# PicoMiteVGAV1_0.net
KiCad netlist of a schematic drawn in EasyEDA Pro
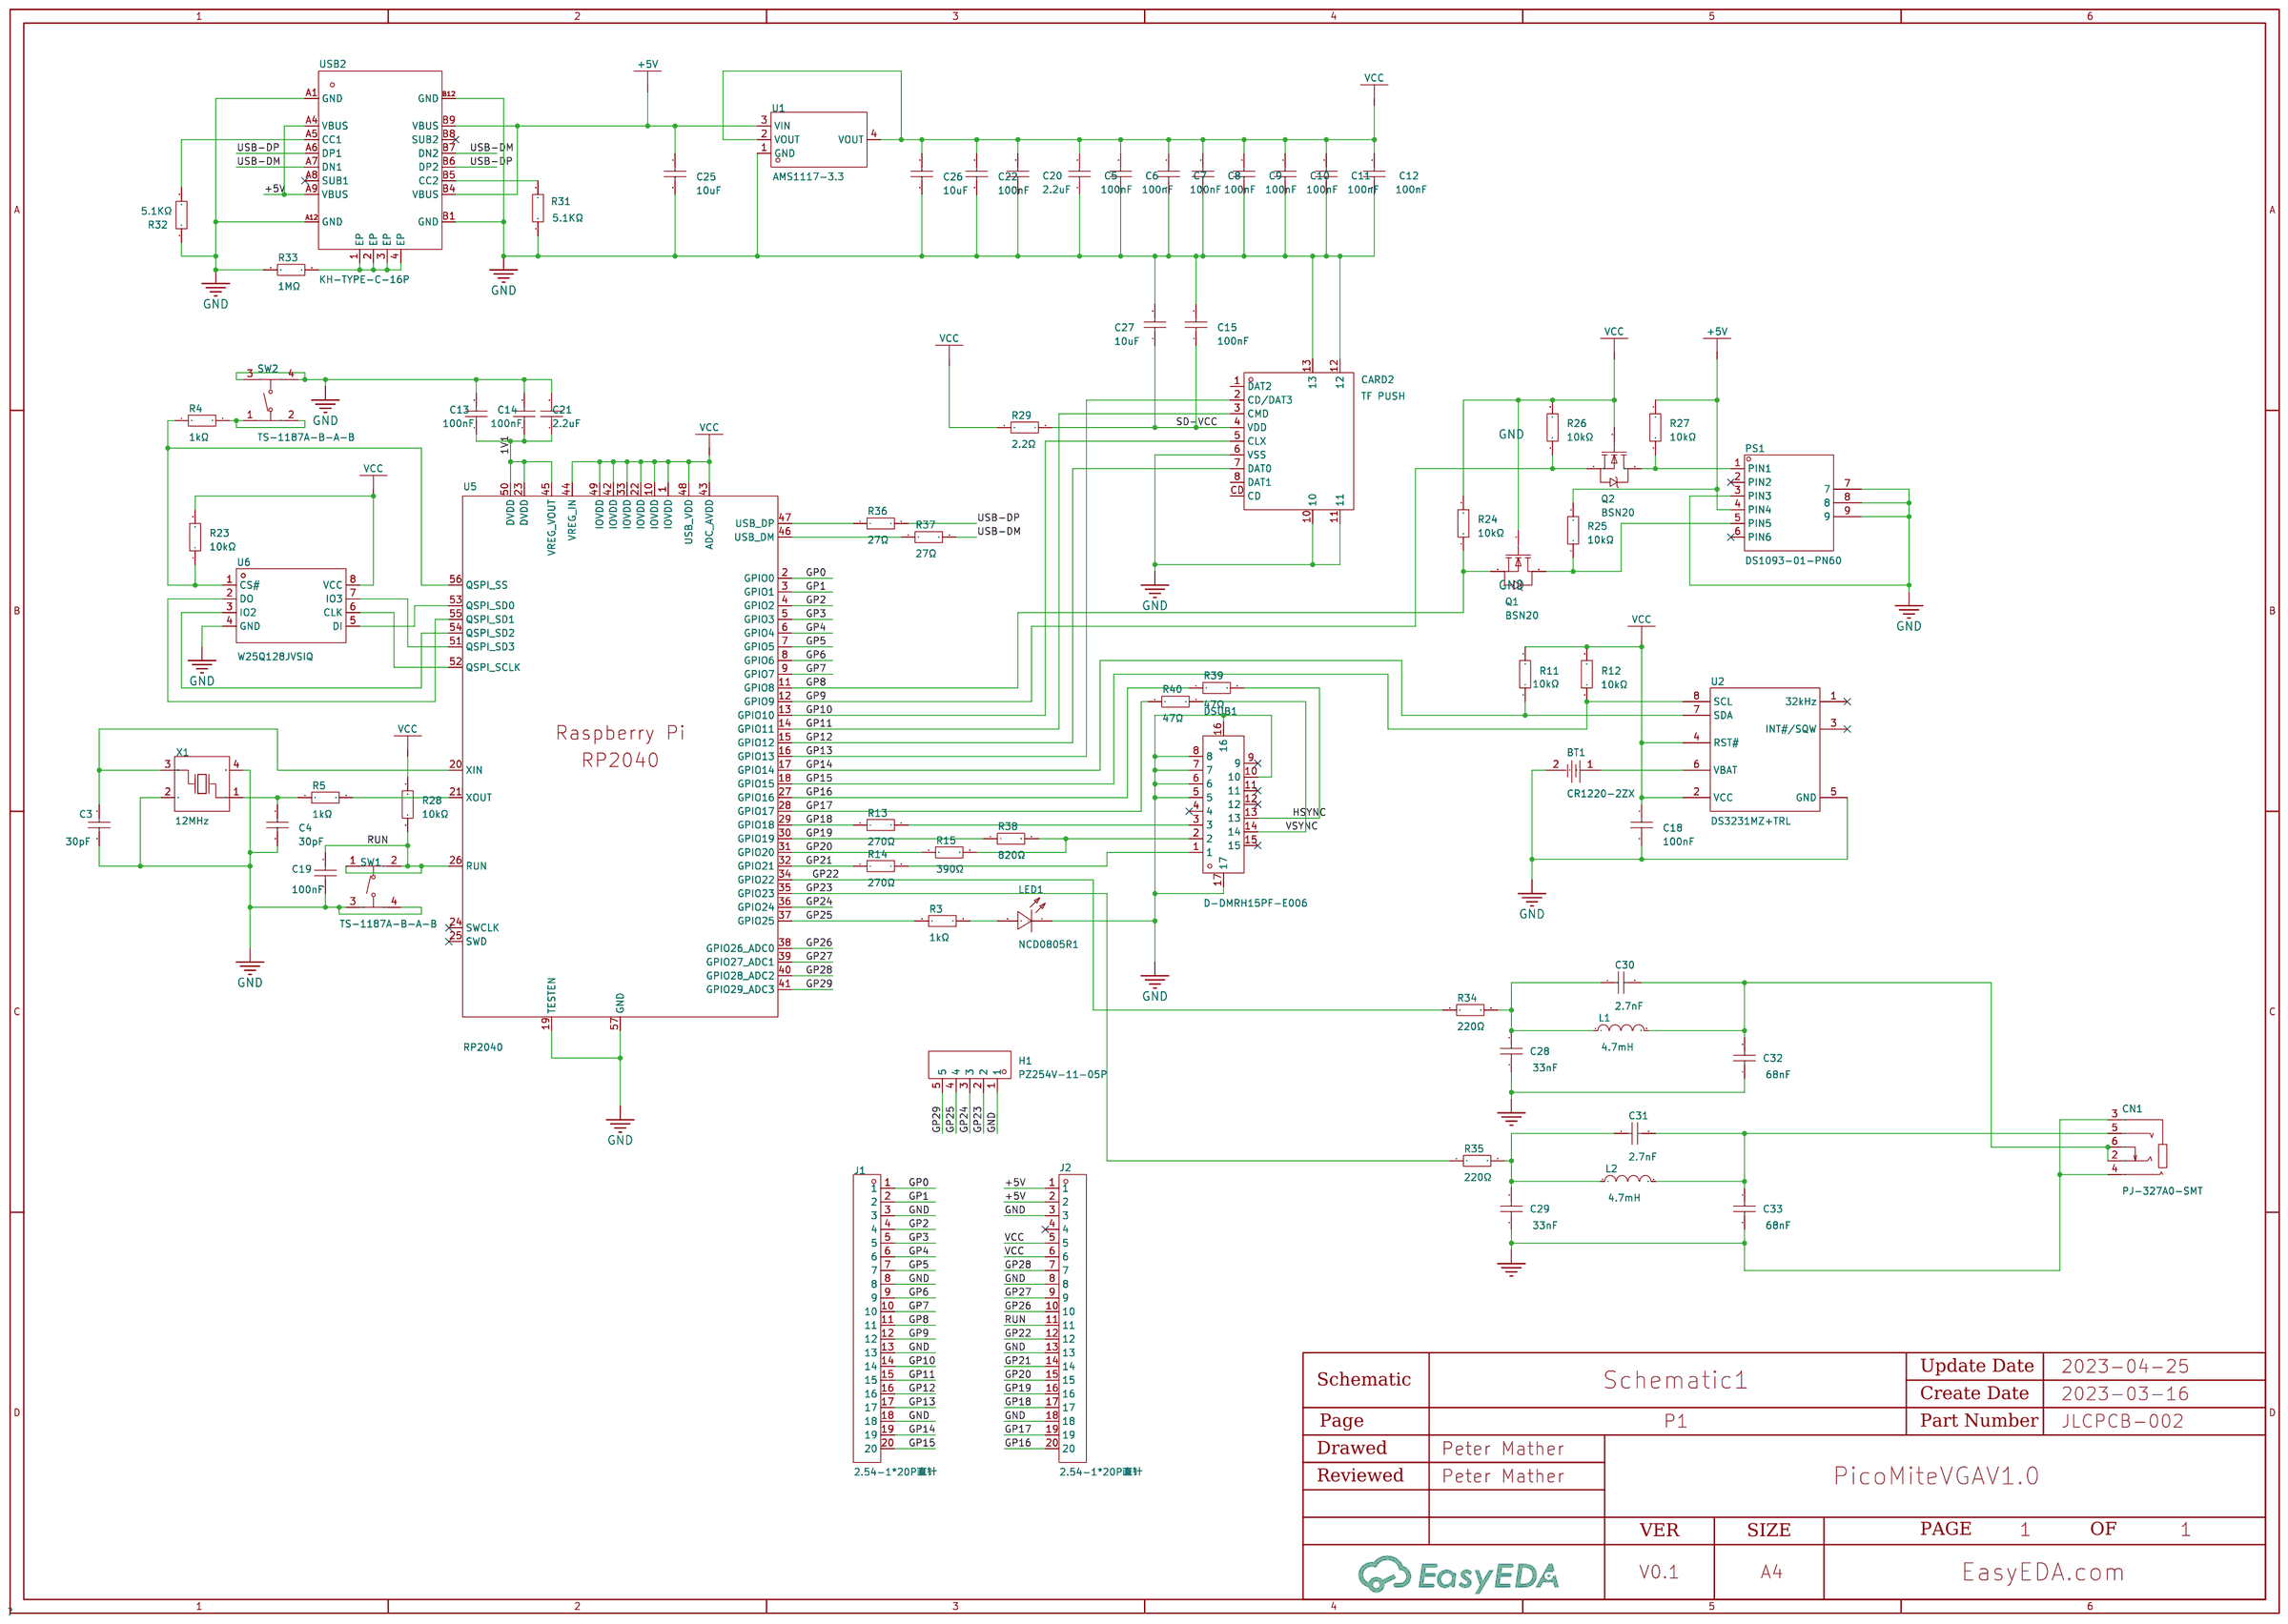
[diagram p0: schematic sheet]

(export (version "E")
  (design (tool "Eeschema 10.0.6"))
  (components
    (comp (ref "BT1")
      (value "CR1220-2ZX")
      (footprint "easyedapro:BAT-SMD_CR1220-2ZX")
      (fields (field (name "Manufacturer") "Q&J"))
      (libsource (lib "easyedapro") (part "CR1220-2ZX"))
    )
    (comp (ref "C3")
      (value "30pF")
      (footprint "easyedapro:C0805")
      (fields (field (name "Manufacturer Part") "0402CG300J500NT") (field (name "Manufacturer") "FH(风华)"))
      (libsource (lib "easyedapro") (part "CC0805JRNPO9BN300"))
    )
    (comp (ref "C4")
      (value "30pF")
      (footprint "easyedapro:C0805")
      (fields (field (name "Manufacturer Part") "0402CG300J500NT") (field (name "Manufacturer") "FH(风华)"))
      (libsource (lib "easyedapro") (part "CC0805JRNPO9BN300"))
    )
    (comp (ref "C5")
      (value "100nF")
      (footprint "easyedapro:C0603")
      (fields
        (field (name "Manufacturer Part") "CL05B104KO5NNNC")
        (field (name "Manufacturer") "SAMSUNG(三星)")
      )
      (libsource (lib "easyedapro") (part "CL10A225KO8NNNC"))
    )
    (comp (ref "C6")
      (value "100nF")
      (footprint "easyedapro:C0603")
      (fields
        (field (name "Manufacturer Part") "CL05B104KO5NNNC")
        (field (name "Manufacturer") "SAMSUNG(三星)")
      )
      (libsource (lib "easyedapro") (part "CL10A225KO8NNNC"))
    )
    (comp (ref "C7")
      (value "100nF")
      (footprint "easyedapro:C0603")
      (fields
        (field (name "Manufacturer Part") "CL05B104KO5NNNC")
        (field (name "Manufacturer") "SAMSUNG(三星)")
      )
      (libsource (lib "easyedapro") (part "CL10A225KO8NNNC"))
    )
    (comp (ref "C8")
      (value "100nF")
      (footprint "easyedapro:C0603")
      (fields
        (field (name "Manufacturer Part") "CL05B104KO5NNNC")
        (field (name "Manufacturer") "SAMSUNG(三星)")
      )
      (libsource (lib "easyedapro") (part "CL10A225KO8NNNC"))
    )
    (comp (ref "C9")
      (value "100nF")
      (footprint "easyedapro:C0603")
      (fields
        (field (name "Manufacturer Part") "CL05B104KO5NNNC")
        (field (name "Manufacturer") "SAMSUNG(三星)")
      )
      (libsource (lib "easyedapro") (part "CL10A225KO8NNNC"))
    )
    (comp (ref "C10")
      (value "100nF")
      (footprint "easyedapro:C0603")
      (fields
        (field (name "Manufacturer Part") "CL05B104KO5NNNC")
        (field (name "Manufacturer") "SAMSUNG(三星)")
      )
      (libsource (lib "easyedapro") (part "CL10A225KO8NNNC"))
    )
    (comp (ref "C11")
      (value "100nF")
      (footprint "easyedapro:C0603")
      (fields
        (field (name "Manufacturer Part") "CL05B104KO5NNNC")
        (field (name "Manufacturer") "SAMSUNG(三星)")
      )
      (libsource (lib "easyedapro") (part "CL10A225KO8NNNC"))
    )
    (comp (ref "C12")
      (value "100nF")
      (footprint "easyedapro:C0603")
      (fields
        (field (name "Manufacturer Part") "CL05B104KO5NNNC")
        (field (name "Manufacturer") "SAMSUNG(三星)")
      )
      (libsource (lib "easyedapro") (part "CL10A225KO8NNNC"))
    )
    (comp (ref "C13")
      (value "100nF")
      (footprint "easyedapro:C0603")
      (fields
        (field (name "Manufacturer Part") "CL05B104KO5NNNC")
        (field (name "Manufacturer") "SAMSUNG(三星)")
      )
      (libsource (lib "easyedapro") (part "CL10A225KO8NNNC"))
    )
    (comp (ref "C14")
      (value "100nF")
      (footprint "easyedapro:C0603")
      (fields
        (field (name "Manufacturer Part") "CL05B104KO5NNNC")
        (field (name "Manufacturer") "SAMSUNG(三星)")
      )
      (libsource (lib "easyedapro") (part "CL10A225KO8NNNC"))
    )
    (comp (ref "C15")
      (value "100nF")
      (footprint "easyedapro:C0603")
      (fields
        (field (name "Manufacturer Part") "CL05B104KO5NNNC")
        (field (name "Manufacturer") "SAMSUNG(三星)")
      )
      (libsource (lib "easyedapro") (part "CL10A225KO8NNNC"))
    )
    (comp (ref "C18")
      (value "100nF")
      (footprint "easyedapro:C0603")
      (fields
        (field (name "Manufacturer Part") "CL05B104KO5NNNC")
        (field (name "Manufacturer") "SAMSUNG(三星)")
      )
      (libsource (lib "easyedapro") (part "CL10A225KO8NNNC"))
    )
    (comp (ref "C19")
      (value "100nF")
      (footprint "easyedapro:C0603")
      (fields
        (field (name "Manufacturer Part") "CL05B104KO5NNNC")
        (field (name "Manufacturer") "SAMSUNG(三星)")
      )
      (libsource (lib "easyedapro") (part "CL10A225KO8NNNC"))
    )
    (comp (ref "C20")
      (value "2.2uF")
      (footprint "easyedapro:C0402_NEW")
      (fields
        (field (name "Manufacturer Part") "CL10A225KO8NNNC")
        (field (name "Manufacturer") "SAMSUNG(三星)")
      )
      (libsource (lib "easyedapro") (part "CL05B104KO5NNNC"))
    )
    (comp (ref "C21")
      (value "2.2uF")
      (footprint "easyedapro:C0402_NEW")
      (fields
        (field (name "Manufacturer Part") "CL10A225KO8NNNC")
        (field (name "Manufacturer") "SAMSUNG(三星)")
      )
      (libsource (lib "easyedapro") (part "CL05B104KO5NNNC"))
    )
    (comp (ref "C22")
      (value "100nF")
      (footprint "easyedapro:C0603")
      (fields
        (field (name "Manufacturer Part") "CL05B104KO5NNNC")
        (field (name "Manufacturer") "SAMSUNG(三星)")
      )
      (libsource (lib "easyedapro") (part "CL10A225KO8NNNC"))
    )
    (comp (ref "C25")
      (value "10uF")
      (footprint "easyedapro:C1206")
      (fields
        (field (name "Manufacturer Part") "CL31A106KBHNNNE")
        (field (name "Manufacturer") "SAMSUNG(三星)")
      )
      (libsource (lib "easyedapro") (part "CL31A106KBHNNNE"))
    )
    (comp (ref "C26")
      (value "10uF")
      (footprint "easyedapro:C1206")
      (fields
        (field (name "Manufacturer Part") "CL31A106KBHNNNE")
        (field (name "Manufacturer") "SAMSUNG(三星)")
      )
      (libsource (lib "easyedapro") (part "CL31A106KBHNNNE"))
    )
    (comp (ref "C27")
      (value "10uF")
      (footprint "easyedapro:C1206")
      (fields
        (field (name "Manufacturer Part") "CL31A106KBHNNNE")
        (field (name "Manufacturer") "SAMSUNG(三星)")
      )
      (libsource (lib "easyedapro") (part "CL31A106KBHNNNE"))
    )
    (comp (ref "C28")
      (value "33nF")
      (footprint "easyedapro:C0603")
      (fields
        (field (name "Manufacturer Part") "CL10B333KB8NNNC")
        (field (name "Manufacturer") "SAMSUNG(三星)")
        (field (name "Tolerance") "±10%")
      )
      (libsource (lib "easyedapro") (part "CL10B333KB8NNNC"))
    )
    (comp (ref "C29")
      (value "33nF")
      (footprint "easyedapro:C0603")
      (fields
        (field (name "Manufacturer Part") "CL10B333KB8NNNC")
        (field (name "Manufacturer") "SAMSUNG(三星)")
      )
      (libsource (lib "easyedapro") (part "CL10B333KB8NNNC"))
    )
    (comp (ref "C30")
      (value "2.7nF")
      (footprint "easyedapro:C0603")
      (fields (field (name "Manufacturer Part") "0603B272K500NT") (field (name "Manufacturer") "FH(风华)"))
      (libsource (lib "easyedapro") (part "0603B272K500NT"))
    )
    (comp (ref "C31")
      (value "2.7nF")
      (footprint "easyedapro:C0603")
      (fields (field (name "Manufacturer Part") "0603B272K500NT") (field (name "Manufacturer") "FH(风华)"))
      (libsource (lib "easyedapro") (part "0603B272K500NT"))
    )
    (comp (ref "C32")
      (value "68nF")
      (footprint "easyedapro:C0603")
      (fields
        (field (name "Manufacturer Part") "CL10B683KB8NNNC")
        (field (name "Manufacturer") "SAMSUNG(三星)")
        (field (name "Tolerance") "±10%")
      )
      (libsource (lib "easyedapro") (part "CL10B683KB8NNNC"))
    )
    (comp (ref "C33")
      (value "68nF")
      (footprint "easyedapro:C0603")
      (fields
        (field (name "Manufacturer Part") "CL10B683KB8NNNC")
        (field (name "Manufacturer") "SAMSUNG(三星)")
      )
      (libsource (lib "easyedapro") (part "CL10B683KB8NNNC"))
    )
    (comp (ref "CARD2")
      (value "TF PUSH")
      (footprint "easyedapro:TF-SMD_TF-PUSH")
      (fields (field (name "Manufacturer") "SHOU HAN(首韩)"))
      (libsource (lib "easyedapro") (part "TF PUSH"))
    )
    (comp (ref "CN1")
      (value "PJ-327A0-SMT")
      (footprint "easyedapro:AUDIO-SMD_PJ-327A0-SMT")
      (fields (field (name "Manufacturer") "XKB Connectivity(中国星坤)"))
      (libsource (lib "easyedapro") (part "PJ-327A0-SMT"))
    )
    (comp (ref "DSUB1")
      (value "D-DMRH15PF-E006")
      (footprint "easyedapro:DSUB-TH_15P-P2.29-H-F_DDMRH15PFE006")
      (fields (field (name "Manufacturer") "Ckmtw(灿科盟)"))
      (libsource (lib "easyedapro") (part "DDMRH15PFE006"))
    )
    (comp (ref "H1")
      (value "PZ254V-11-05P")
      (footprint "easyedapro:HDR-TH_5P-P2.54-V-M")
      (fields (field (name "Manufacturer") "XFCN(兴飞)"))
      (libsource (lib "easyedapro") (part "PZ254V-11-05P"))
    )
    (comp (ref "J1")
      (value "2.54-1*20P直针")
      (footprint "easyedapro:HDR-TH_20P-P2.54-V-M-1")
      (fields (field (name "Manufacturer") "BOOMELE(博穆精密)"))
      (libsource (lib "easyedapro") (part "Header-Male-2.54_1x20"))
    )
    (comp (ref "J2")
      (value "2.54-1*20P直针")
      (footprint "easyedapro:HDR-TH_20P-P2.54-V-M-1")
      (fields (field (name "Manufacturer") "BOOMELE(博穆精密)"))
      (libsource (lib "easyedapro") (part "Header-Male-2.54_1x20"))
    )
    (comp (ref "L1")
      (value "4.7mH")
      (footprint "easyedapro:IND-SMD_L6.0-W6.0")
      (fields (field (name "Manufacturer Part") "YNR6045-472M") (field (name "Manufacturer") "YJYCOIN(益嘉源)"))
      (libsource (lib "easyedapro") (part "YNR6045-472M"))
    )
    (comp (ref "L2")
      (value "4.7mH")
      (footprint "easyedapro:IND-SMD_L6.0-W6.0")
      (fields (field (name "Manufacturer Part") "YNR6045-472M") (field (name "Manufacturer") "YJYCOIN(益嘉源)"))
      (libsource (lib "easyedapro") (part "YNR6045-472M"))
    )
    (comp (ref "LED1")
      (value "NCD0805R1")
      (footprint "easyedapro:LED0805-RD")
      (description "Emitted Color:红灯")
      (fields (field (name "Manufacturer") "国星光电"))
      (libsource (lib "easyedapro") (part "FC-2012HRK-620D"))
    )
    (comp (ref "PS1")
      (value "DS1093-01-PN60")
      (footprint "easyedapro:CONN-TH_DS1093-01-PN60")
      (fields (field (name "Manufacturer") "CONNFLY"))
      (libsource (lib "easyedapro") (part "DS1093-01-PN60"))
    )
    (comp (ref "Q1")
      (value "BSN20")
      (footprint "easyedapro:SOT-23-3_L2.9-W1.6-P1.90-LS2.8-BR")
      (fields (field (name "Manufacturer") "SHIKUES(时科)"))
      (libsource (lib "easyedapro") (part "BSN20"))
    )
    (comp (ref "Q2")
      (value "BSN20")
      (footprint "easyedapro:SOT-23-3_L2.9-W1.6-P1.90-LS2.8-BR")
      (fields (field (name "Manufacturer") "SHIKUES(时科)"))
      (libsource (lib "easyedapro") (part "BSN20"))
    )
    (comp (ref "R3")
      (value "1kΩ")
      (footprint "easyedapro:R0603")
      (fields
        (field (name "Manufacturer Part") "0603WAF1001T5E")
        (field (name "Manufacturer") "UNI-ROYAL(厚声)")
      )
      (libsource (lib "easyedapro") (part "0603WAF1001T5E"))
    )
    (comp (ref "R4")
      (value "1kΩ")
      (footprint "easyedapro:R0603")
      (fields
        (field (name "Manufacturer Part") "0603WAF1001T5E")
        (field (name "Manufacturer") "UNI-ROYAL(厚声)")
      )
      (libsource (lib "easyedapro") (part "0603WAF1001T5E"))
    )
    (comp (ref "R5")
      (value "1kΩ")
      (footprint "easyedapro:R0603")
      (fields
        (field (name "Manufacturer Part") "0603WAF1001T5E")
        (field (name "Manufacturer") "UNI-ROYAL(厚声)")
      )
      (libsource (lib "easyedapro") (part "0603WAF1001T5E"))
    )
    (comp (ref "R11")
      (value "10kΩ")
      (footprint "easyedapro:R0805")
      (fields
        (field (name "Manufacturer Part") "0805W8F1002T5E")
        (field (name "Manufacturer") "UNI-ROYAL(厚声)")
      )
      (libsource (lib "easyedapro") (part "0805W8F1002T5E"))
    )
    (comp (ref "R12")
      (value "10kΩ")
      (footprint "easyedapro:R0805")
      (fields
        (field (name "Manufacturer Part") "0805W8F1002T5E")
        (field (name "Manufacturer") "UNI-ROYAL(厚声)")
      )
      (libsource (lib "easyedapro") (part "0805W8F1002T5E"))
    )
    (comp (ref "R13")
      (value "270Ω")
      (footprint "easyedapro:R0603")
      (fields
        (field (name "Manufacturer Part") "0603WAF2700T5E")
        (field (name "Manufacturer") "UNI-ROYAL(厚声)")
      )
      (libsource (lib "easyedapro") (part "0603WAF2700T5E"))
    )
    (comp (ref "R14")
      (value "270Ω")
      (footprint "easyedapro:R0603")
      (fields
        (field (name "Manufacturer Part") "0603WAF2700T5E")
        (field (name "Manufacturer") "UNI-ROYAL(厚声)")
      )
      (libsource (lib "easyedapro") (part "0603WAF2700T5E"))
    )
    (comp (ref "R15")
      (value "390Ω")
      (footprint "easyedapro:R0603")
      (fields
        (field (name "Manufacturer Part") "0603WAF3900T5E")
        (field (name "Manufacturer") "UNI-ROYAL(厚声)")
      )
      (libsource (lib "easyedapro") (part "0603WAF3900T5E"))
    )
    (comp (ref "R23")
      (value "10kΩ")
      (footprint "easyedapro:R0402")
      (fields
        (field (name "Manufacturer Part") "0402WGF1002TCE")
        (field (name "Manufacturer") "UNI-ROYAL(厚声)")
      )
      (libsource (lib "easyedapro") (part "0402WGF1002TCE"))
    )
    (comp (ref "R24")
      (value "10kΩ")
      (footprint "easyedapro:R0402")
      (fields
        (field (name "Manufacturer Part") "0402WGF1002TCE")
        (field (name "Manufacturer") "UNI-ROYAL(厚声)")
      )
      (libsource (lib "easyedapro") (part "0402WGF1002TCE"))
    )
    (comp (ref "R25")
      (value "10kΩ")
      (footprint "easyedapro:R0402")
      (fields
        (field (name "Manufacturer Part") "0402WGF1002TCE")
        (field (name "Manufacturer") "UNI-ROYAL(厚声)")
      )
      (libsource (lib "easyedapro") (part "0402WGF1002TCE"))
    )
    (comp (ref "R26")
      (value "10kΩ")
      (footprint "easyedapro:R0402")
      (fields
        (field (name "Manufacturer Part") "0402WGF1002TCE")
        (field (name "Manufacturer") "UNI-ROYAL(厚声)")
      )
      (libsource (lib "easyedapro") (part "0402WGF1002TCE"))
    )
    (comp (ref "R27")
      (value "10kΩ")
      (footprint "easyedapro:R0402")
      (fields
        (field (name "Manufacturer Part") "0402WGF1002TCE")
        (field (name "Manufacturer") "UNI-ROYAL(厚声)")
      )
      (libsource (lib "easyedapro") (part "0402WGF1002TCE"))
    )
    (comp (ref "R28")
      (value "10kΩ")
      (footprint "easyedapro:R0402")
      (fields
        (field (name "Manufacturer Part") "0402WGF1002TCE")
        (field (name "Manufacturer") "UNI-ROYAL(厚声)")
      )
      (libsource (lib "easyedapro") (part "0402WGF1002TCE"))
    )
    (comp (ref "R29")
      (value "2.2Ω")
      (footprint "easyedapro:R0805")
      (fields (field (name "Manufacturer") "UNI-ROYAL(厚声)"))
      (libsource (lib "easyedapro") (part "0805W8F220KT5E"))
    )
    (comp (ref "R31")
      (value "5.1kΩ")
      (footprint "easyedapro:R0603")
      (fields
        (field (name "Manufacturer Part") "5.1KΩ")
        (field (name "Manufacturer") "UNI-ROYAL(厚声)")
        (field (name "Tolerance") "±1%")
      )
      (libsource (lib "easyedapro") (part "0603WAF5101T5E"))
    )
    (comp (ref "R32")
      (value "5.1kΩ")
      (footprint "easyedapro:R0603")
      (fields
        (field (name "Manufacturer Part") "5.1KΩ")
        (field (name "Manufacturer") "UNI-ROYAL(厚声)")
        (field (name "Tolerance") "±1%")
      )
      (libsource (lib "easyedapro") (part "0603WAF5101T5E"))
    )
    (comp (ref "R33")
      (value "1MΩ")
      (footprint "easyedapro:R0603")
      (fields
        (field (name "Manufacturer Part") "0402WGF1004TCE")
        (field (name "Manufacturer") "UNI-ROYAL(厚声)")
        (field (name "Tolerance") "±1%")
      )
      (libsource (lib "easyedapro") (part "0603WAF1004T5E"))
    )
    (comp (ref "R34")
      (value "220Ω")
      (footprint "easyedapro:R0603")
      (fields
        (field (name "Manufacturer Part") "0603WAF2200T5E")
        (field (name "Manufacturer") "UNI-ROYAL(厚声)")
      )
      (libsource (lib "easyedapro") (part "0603WAF2200T5E"))
    )
    (comp (ref "R35")
      (value "220Ω")
      (footprint "easyedapro:R0603")
      (fields
        (field (name "Manufacturer Part") "0603WAF2200T5E")
        (field (name "Manufacturer") "UNI-ROYAL(厚声)")
      )
      (libsource (lib "easyedapro") (part "0603WAF2200T5E"))
    )
    (comp (ref "R36")
      (value "27Ω")
      (footprint "easyedapro:R0603")
      (fields
        (field (name "Manufacturer Part") "0603WAF270JT5E")
        (field (name "Manufacturer") "UNI-ROYAL(厚声)")
      )
      (libsource (lib "easyedapro") (part "0603WAF270JT5E"))
    )
    (comp (ref "R37")
      (value "27Ω")
      (footprint "easyedapro:R0603")
      (fields
        (field (name "Manufacturer Part") "0603WAF270JT5E")
        (field (name "Manufacturer") "UNI-ROYAL(厚声)")
      )
      (libsource (lib "easyedapro") (part "0603WAF270JT5E"))
    )
    (comp (ref "R38")
      (value "820Ω")
      (footprint "easyedapro:R0603")
      (fields
        (field (name "Manufacturer Part") "0603WAF8200T5E")
        (field (name "Manufacturer") "UNI-ROYAL(厚声)")
      )
      (libsource (lib "easyedapro") (part "0603WAF8200T5E"))
    )
    (comp (ref "R39")
      (value "47Ω")
      (footprint "easyedapro:R0805")
      (fields
        (field (name "Manufacturer Part") "0805W8F470JT5E")
        (field (name "Manufacturer") "UNI-ROYAL(厚声)")
      )
      (libsource (lib "easyedapro") (part "0805W8F470JT5E"))
    )
    (comp (ref "R40")
      (value "47Ω")
      (footprint "easyedapro:R0805")
      (fields
        (field (name "Manufacturer Part") "0805W8F470JT5E")
        (field (name "Manufacturer") "UNI-ROYAL(厚声)")
      )
      (libsource (lib "easyedapro") (part "0805W8F470JT5E"))
    )
    (comp (ref "SW1")
      (value "TS-1187A-B-A-B")
      (footprint "easyedapro:SW-SMD_4P-L5.1-W5.1-P3.70-LS6.5-TL-2")
      (fields (field (name "Manufacturer") "XKB Connectivity(中国星坤)"))
      (libsource (lib "easyedapro") (part "TS-1187A-B-A-B"))
    )
    (comp (ref "SW2")
      (value "TS-1187A-B-A-B")
      (footprint "easyedapro:SW-SMD_4P-L5.1-W5.1-P3.70-LS6.5-TL-2")
      (fields (field (name "Manufacturer") "XKB Connectivity(中国星坤)"))
      (libsource (lib "easyedapro") (part "TS-1187A-B-A-B"))
    )
    (comp (ref "U1")
      (value "AMS1117-3.3")
      (footprint "easyedapro:SOT-223-3_L6.5-W3.4-P2.30-LS7.0-BR")
      (fields (field (name "Manufacturer") "AMS"))
      (libsource (lib "easyedapro") (part "AMS1117-3.3"))
    )
    (comp (ref "U2")
      (value "DS3231MZ+TRL")
      (footprint "easyedapro:SOIC-8_L4.9-W3.9-P1.27-LS6.0-BL")
      (fields (field (name "Manufacturer") "MAXIM(美信)"))
      (libsource (lib "easyedapro") (part "DS3231MZ+"))
    )
    (comp (ref "U5")
      (value "RP2040")
      (footprint "easyedapro:LQFN-56_L7.0-W7.0-P0.4-EP")
      (fields (field (name "Manufacturer") "Raspberry Pi(树莓派)"))
      (libsource (lib "easyedapro") (part "RP2040"))
    )
    (comp (ref "U6")
      (value "W25Q128JVSIQ")
      (footprint "easyedapro:SOIC-8_L5.3-W5.3-P1.27-LS8.0-BL")
      (fields (field (name "Manufacturer") "WINBOND(华邦)"))
      (libsource (lib "easyedapro") (part "W25Q128JVSIQTR"))
    )
    (comp (ref "USB2")
      (value "KH-TYPE-C-16P")
      (footprint "easyedapro:USB-C-SMD_KH-TYPE-C-16P")
      (fields (field (name "Manufacturer") "kinghelm(金航标)"))
      (libsource (lib "easyedapro") (part "KH-TYPE-C-16P"))
    )
    (comp (ref "X1")
      (value "12MHz")
      (footprint "easyedapro:OSC-SMD_4P-L3.2-W2.5-BL")
      (fields (field (name "Manufacturer Part") "X322512MSB4SI") (field (name "Manufacturer") "YXC(扬兴晶振)"))
      (libsource (lib "easyedapro") (part "X322512MSB4SI"))
    )
  )
  (nets
    (net (code "1") (name "+5V") (class "Default")
      (node (ref "C25") (pin "2") (pinfunction "2_2") (pintype "input"))
      (node (ref "J2") (pin "1") (pinfunction "1_1") (pintype "input"))
      (node (ref "J2") (pin "2") (pinfunction "2_2") (pintype "input"))
      (node (ref "PS1") (pin "4") (pinfunction "PIN4_4") (pintype "input"))
      (node (ref "R25") (pin "2") (pinfunction "2_2") (pintype "input"))
      (node (ref "R27") (pin "2") (pinfunction "2_2") (pintype "input"))
      (node (ref "U1") (pin "3") (pinfunction "VIN_3") (pintype "input"))
      (node (ref "USB2") (pin "A4") (pinfunction "VBUS_A4") (pintype "input"))
      (node (ref "USB2") (pin "A9") (pinfunction "VBUS_A9") (pintype "input"))
      (node (ref "USB2") (pin "B4") (pinfunction "VBUS_B4") (pintype "input"))
      (node (ref "USB2") (pin "B9") (pinfunction "VBUS_B9") (pintype "input"))
    )
    (net (code "2") (name "/1V1") (class "Default")
      (node (ref "C13") (pin "1") (pinfunction "1_1") (pintype "input"))
      (node (ref "C14") (pin "1") (pinfunction "1_1") (pintype "input"))
      (node (ref "C21") (pin "1") (pinfunction "1_1") (pintype "input"))
      (node (ref "U5") (pin "23") (pinfunction "DVDD_23") (pintype "bidirectional"))
      (node (ref "U5") (pin "45") (pinfunction "VREG_VOUT_45") (pintype "bidirectional"))
      (node (ref "U5") (pin "50") (pinfunction "DVDD_50") (pintype "bidirectional"))
    )
    (net (code "3") (name "/GP0") (class "Default")
      (node (ref "J1") (pin "1") (pinfunction "1_1") (pintype "input"))
      (node (ref "U5") (pin "2") (pinfunction "GPIO0_2") (pintype "bidirectional"))
    )
    (net (code "4") (name "/GP1") (class "Default")
      (node (ref "J1") (pin "2") (pinfunction "2_2") (pintype "input"))
      (node (ref "U5") (pin "3") (pinfunction "GPIO1_3") (pintype "bidirectional"))
    )
    (net (code "5") (name "/GP2") (class "Default")
      (node (ref "J1") (pin "4") (pinfunction "4_4") (pintype "input"))
      (node (ref "U5") (pin "4") (pinfunction "GPIO2_4") (pintype "bidirectional"))
    )
    (net (code "6") (name "/GP3") (class "Default")
      (node (ref "J1") (pin "5") (pinfunction "5_5") (pintype "input"))
      (node (ref "U5") (pin "5") (pinfunction "GPIO3_5") (pintype "bidirectional"))
    )
    (net (code "7") (name "/GP4") (class "Default")
      (node (ref "J1") (pin "6") (pinfunction "6_6") (pintype "input"))
      (node (ref "U5") (pin "6") (pinfunction "GPIO4_6") (pintype "bidirectional"))
    )
    (net (code "8") (name "/GP5") (class "Default")
      (node (ref "J1") (pin "7") (pinfunction "7_7") (pintype "input"))
      (node (ref "U5") (pin "7") (pinfunction "GPIO5_7") (pintype "bidirectional"))
    )
    (net (code "9") (name "/GP6") (class "Default")
      (node (ref "J1") (pin "9") (pinfunction "9_9") (pintype "input"))
      (node (ref "U5") (pin "8") (pinfunction "GPIO6_8") (pintype "bidirectional"))
    )
    (net (code "10") (name "/GP7") (class "Default")
      (node (ref "J1") (pin "10") (pinfunction "10_10") (pintype "input"))
      (node (ref "U5") (pin "9") (pinfunction "GPIO7_9") (pintype "bidirectional"))
    )
    (net (code "11") (name "/GP8") (class "Default")
      (node (ref "J1") (pin "11") (pinfunction "11_11") (pintype "input"))
      (node (ref "Q1") (pin "2") (pinfunction "S_2") (pintype "input"))
      (node (ref "R24") (pin "1") (pinfunction "1_1") (pintype "input"))
      (node (ref "U5") (pin "11") (pinfunction "GPIO8_11") (pintype "bidirectional"))
    )
    (net (code "12") (name "/GP9") (class "Default")
      (node (ref "J1") (pin "12") (pinfunction "12_12") (pintype "input"))
      (node (ref "Q2") (pin "2") (pinfunction "S_2") (pintype "input"))
      (node (ref "R26") (pin "1") (pinfunction "1_1") (pintype "input"))
      (node (ref "U5") (pin "12") (pinfunction "GPIO9_12") (pintype "bidirectional"))
    )
    (net (code "13") (name "/GP10") (class "Default")
      (node (ref "CARD2") (pin "5") (pinfunction "CLX_5") (pintype "input"))
      (node (ref "J1") (pin "14") (pinfunction "14_14") (pintype "input"))
      (node (ref "U5") (pin "13") (pinfunction "GPIO10_13") (pintype "bidirectional"))
    )
    (net (code "14") (name "/GP11") (class "Default")
      (node (ref "CARD2") (pin "3") (pinfunction "CMD_3") (pintype "input"))
      (node (ref "J1") (pin "15") (pinfunction "15_15") (pintype "input"))
      (node (ref "U5") (pin "14") (pinfunction "GPIO11_14") (pintype "bidirectional"))
    )
    (net (code "15") (name "/GP12") (class "Default")
      (node (ref "CARD2") (pin "7") (pinfunction "DAT0_7") (pintype "input"))
      (node (ref "J1") (pin "16") (pinfunction "16_16") (pintype "input"))
      (node (ref "U5") (pin "15") (pinfunction "GPIO12_15") (pintype "bidirectional"))
    )
    (net (code "16") (name "/GP13") (class "Default")
      (node (ref "CARD2") (pin "2") (pinfunction "CD/DAT3_2") (pintype "input"))
      (node (ref "J1") (pin "17") (pinfunction "17_17") (pintype "input"))
      (node (ref "U5") (pin "16") (pinfunction "GPIO13_16") (pintype "bidirectional"))
    )
    (net (code "17") (name "/GP14") (class "Default")
      (node (ref "J1") (pin "19") (pinfunction "19_19") (pintype "input"))
      (node (ref "R11") (pin "1") (pinfunction "1_1") (pintype "input"))
      (node (ref "U2") (pin "7") (pinfunction "SDA_7") (pintype "bidirectional"))
      (node (ref "U5") (pin "17") (pinfunction "GPIO14_17") (pintype "bidirectional"))
    )
    (net (code "18") (name "/GP15") (class "Default")
      (node (ref "J1") (pin "20") (pinfunction "20_20") (pintype "input"))
      (node (ref "R12") (pin "1") (pinfunction "1_1") (pintype "input"))
      (node (ref "U2") (pin "8") (pinfunction "SCL_8") (pintype "input"))
      (node (ref "U5") (pin "18") (pinfunction "GPIO15_18") (pintype "bidirectional"))
    )
    (net (code "19") (name "/GP16") (class "Default")
      (node (ref "J2") (pin "20") (pinfunction "20_20") (pintype "input"))
      (node (ref "R39") (pin "1") (pinfunction "1_1") (pintype "input"))
      (node (ref "U5") (pin "27") (pinfunction "GPIO16_27") (pintype "bidirectional"))
    )
    (net (code "20") (name "/GP17") (class "Default")
      (node (ref "J2") (pin "19") (pinfunction "19_19") (pintype "input"))
      (node (ref "R40") (pin "1") (pinfunction "1_1") (pintype "input"))
      (node (ref "U5") (pin "28") (pinfunction "GPIO17_28") (pintype "bidirectional"))
    )
    (net (code "21") (name "/GP18") (class "Default")
      (node (ref "J2") (pin "17") (pinfunction "17_17") (pintype "input"))
      (node (ref "R13") (pin "1") (pinfunction "1_1") (pintype "input"))
      (node (ref "U5") (pin "29") (pinfunction "GPIO18_29") (pintype "bidirectional"))
    )
    (net (code "22") (name "/GP19") (class "Default")
      (node (ref "J2") (pin "16") (pinfunction "16_16") (pintype "input"))
      (node (ref "R38") (pin "1") (pinfunction "1_1") (pintype "input"))
      (node (ref "U5") (pin "30") (pinfunction "GPIO19_30") (pintype "bidirectional"))
    )
    (net (code "23") (name "/GP20") (class "Default")
      (node (ref "J2") (pin "15") (pinfunction "15_15") (pintype "input"))
      (node (ref "R15") (pin "1") (pinfunction "1_1") (pintype "input"))
      (node (ref "U5") (pin "31") (pinfunction "GPIO20_31") (pintype "bidirectional"))
    )
    (net (code "24") (name "/GP21") (class "Default")
      (node (ref "J2") (pin "14") (pinfunction "14_14") (pintype "input"))
      (node (ref "R14") (pin "1") (pinfunction "1_1") (pintype "input"))
      (node (ref "U5") (pin "32") (pinfunction "GPIO21_32") (pintype "bidirectional"))
    )
    (net (code "25") (name "/GP22") (class "Default")
      (node (ref "J2") (pin "12") (pinfunction "12_12") (pintype "input"))
      (node (ref "R34") (pin "1") (pinfunction "1_1") (pintype "input"))
      (node (ref "U5") (pin "34") (pinfunction "GPIO22_34") (pintype "bidirectional"))
    )
    (net (code "26") (name "/GP23") (class "Default")
      (node (ref "H1") (pin "2") (pinfunction "2_2") (pintype "input"))
      (node (ref "R35") (pin "1") (pinfunction "1_1") (pintype "input"))
      (node (ref "U5") (pin "35") (pinfunction "GPIO23_35") (pintype "bidirectional"))
    )
    (net (code "27") (name "/GP24") (class "Default")
      (node (ref "H1") (pin "3") (pinfunction "3_3") (pintype "input"))
      (node (ref "U5") (pin "36") (pinfunction "GPIO24_36") (pintype "bidirectional"))
    )
    (net (code "28") (name "/GP25") (class "Default")
      (node (ref "H1") (pin "4") (pinfunction "4_4") (pintype "input"))
      (node (ref "R3") (pin "1") (pinfunction "1_1") (pintype "input"))
      (node (ref "U5") (pin "37") (pinfunction "GPIO25_37") (pintype "bidirectional"))
    )
    (net (code "29") (name "/GP26") (class "Default")
      (node (ref "J2") (pin "10") (pinfunction "10_10") (pintype "input"))
      (node (ref "U5") (pin "38") (pinfunction "GPIO26_ADC0_38") (pintype "bidirectional"))
    )
    (net (code "30") (name "/GP27") (class "Default")
      (node (ref "J2") (pin "9") (pinfunction "9_9") (pintype "input"))
      (node (ref "U5") (pin "39") (pinfunction "GPIO27_ADC1_39") (pintype "bidirectional"))
    )
    (net (code "31") (name "/GP28") (class "Default")
      (node (ref "J2") (pin "7") (pinfunction "7_7") (pintype "input"))
      (node (ref "U5") (pin "40") (pinfunction "GPIO28_ADC2_40") (pintype "bidirectional"))
    )
    (net (code "32") (name "/GP29") (class "Default")
      (node (ref "H1") (pin "5") (pinfunction "5_5") (pintype "input"))
      (node (ref "U5") (pin "41") (pinfunction "GPIO29_ADC3_41") (pintype "bidirectional"))
    )
    (net (code "33") (name "/HSYNC") (class "Default")
      (node (ref "DSUB1") (pin "13") (pinfunction "13_13") (pintype "input"))
      (node (ref "R39") (pin "2") (pinfunction "2_2") (pintype "input"))
    )
    (net (code "34") (name "/RUN") (class "Default")
      (node (ref "C19") (pin "2") (pinfunction "2_2") (pintype "input"))
      (node (ref "J2") (pin "11") (pinfunction "11_11") (pintype "input"))
      (node (ref "R28") (pin "1") (pinfunction "1_1") (pintype "input"))
      (node (ref "SW1") (pin "1") (pinfunction "A_1") (pintype "input"))
      (node (ref "SW1") (pin "2") (pinfunction "B_2") (pintype "input"))
      (node (ref "U5") (pin "26") (pinfunction "RUN_26") (pintype "input"))
    )
    (net (code "35") (name "/SD-VCC") (class "Default")
      (node (ref "C15") (pin "1") (pinfunction "1_1") (pintype "input"))
      (node (ref "C27") (pin "1") (pinfunction "1_1") (pintype "input"))
      (node (ref "CARD2") (pin "4") (pinfunction "VDD_4") (pintype "input"))
      (node (ref "R29") (pin "2") (pinfunction "2_2") (pintype "input"))
    )
    (net (code "36") (name "/USB-DM") (class "Default")
      (node (ref "R37") (pin "2") (pinfunction "2_2") (pintype "input"))
      (node (ref "USB2") (pin "A7") (pinfunction "DN1_A7") (pintype "input"))
      (node (ref "USB2") (pin "B7") (pinfunction "DN2_B7") (pintype "input"))
    )
    (net (code "37") (name "/USB-DP") (class "Default")
      (node (ref "R36") (pin "2") (pinfunction "2_2") (pintype "input"))
      (node (ref "USB2") (pin "A6") (pinfunction "DP1_A6") (pintype "input"))
      (node (ref "USB2") (pin "B6") (pinfunction "DP2_B6") (pintype "input"))
    )
    (net (code "38") (name "/VSYNC") (class "Default")
      (node (ref "DSUB1") (pin "14") (pinfunction "14_14") (pintype "input"))
      (node (ref "R40") (pin "2") (pinfunction "2_2") (pintype "input"))
    )
    (net (code "39") (name "GND") (class "Default")
      (node (ref "BT1") (pin "2") (pinfunction "2_2") (pintype "input"))
      (node (ref "C10") (pin "1") (pinfunction "1_1") (pintype "input"))
      (node (ref "C11") (pin "1") (pinfunction "1_1") (pintype "input"))
      (node (ref "C12") (pin "1") (pinfunction "1_1") (pintype "input"))
      (node (ref "C13") (pin "2") (pinfunction "2_2") (pintype "input"))
      (node (ref "C14") (pin "2") (pinfunction "2_2") (pintype "input"))
      (node (ref "C15") (pin "2") (pinfunction "2_2") (pintype "input"))
      (node (ref "C18") (pin "1") (pinfunction "1_1") (pintype "input"))
      (node (ref "C19") (pin "1") (pinfunction "1_1") (pintype "input"))
      (node (ref "C20") (pin "1") (pinfunction "1_1") (pintype "input"))
      (node (ref "C21") (pin "2") (pinfunction "2_2") (pintype "input"))
      (node (ref "C22") (pin "1") (pinfunction "1_1") (pintype "input"))
      (node (ref "C25") (pin "1") (pinfunction "1_1") (pintype "input"))
      (node (ref "C26") (pin "1") (pinfunction "1_1") (pintype "input"))
      (node (ref "C27") (pin "2") (pinfunction "2_2") (pintype "input"))
      (node (ref "C28") (pin "1") (pinfunction "1_1") (pintype "input"))
      (node (ref "C29") (pin "1") (pinfunction "1_1") (pintype "input"))
      (node (ref "C3") (pin "1") (pinfunction "1_1") (pintype "input"))
      (node (ref "C32") (pin "1") (pinfunction "1_1") (pintype "input"))
      (node (ref "C33") (pin "1") (pinfunction "1_1") (pintype "input"))
      (node (ref "C4") (pin "1") (pinfunction "1_1") (pintype "input"))
      (node (ref "C5") (pin "1") (pinfunction "1_1") (pintype "input"))
      (node (ref "C6") (pin "1") (pinfunction "1_1") (pintype "input"))
      (node (ref "C7") (pin "1") (pinfunction "1_1") (pintype "input"))
      (node (ref "C8") (pin "1") (pinfunction "1_1") (pintype "input"))
      (node (ref "C9") (pin "1") (pinfunction "1_1") (pintype "input"))
      (node (ref "CARD2") (pin "10") (pinfunction "10_10") (pintype "input"))
      (node (ref "CARD2") (pin "11") (pinfunction "11_11") (pintype "input"))
      (node (ref "CARD2") (pin "12") (pinfunction "12_12") (pintype "input"))
      (node (ref "CARD2") (pin "13") (pinfunction "13_13") (pintype "input"))
      (node (ref "CARD2") (pin "6") (pinfunction "VSS_6") (pintype "input"))
      (node (ref "CN1") (pin "3") (pinfunction "3_3") (pintype "input"))
      (node (ref "CN1") (pin "4") (pinfunction "4_4") (pintype "input"))
      (node (ref "DSUB1") (pin "10") (pinfunction "10_10") (pintype "input"))
      (node (ref "DSUB1") (pin "16") (pinfunction "16_16") (pintype "input"))
      (node (ref "DSUB1") (pin "17") (pinfunction "17_17") (pintype "input"))
      (node (ref "DSUB1") (pin "5") (pinfunction "5_5") (pintype "input"))
      (node (ref "DSUB1") (pin "6") (pinfunction "6_6") (pintype "input"))
      (node (ref "DSUB1") (pin "7") (pinfunction "7_7") (pintype "input"))
      (node (ref "DSUB1") (pin "8") (pinfunction "8_8") (pintype "input"))
      (node (ref "H1") (pin "1") (pinfunction "1_1") (pintype "input"))
      (node (ref "J1") (pin "13") (pinfunction "13_13") (pintype "input"))
      (node (ref "J1") (pin "18") (pinfunction "18_18") (pintype "input"))
      (node (ref "J1") (pin "3") (pinfunction "3_3") (pintype "input"))
      (node (ref "J1") (pin "8") (pinfunction "8_8") (pintype "input"))
      (node (ref "J2") (pin "13") (pinfunction "13_13") (pintype "input"))
      (node (ref "J2") (pin "18") (pinfunction "18_18") (pintype "input"))
      (node (ref "J2") (pin "3") (pinfunction "3_3") (pintype "input"))
      (node (ref "J2") (pin "8") (pinfunction "8_8") (pintype "input"))
      (node (ref "LED1") (pin "1") (pinfunction "-_1") (pintype "input"))
      (node (ref "PS1") (pin "3") (pinfunction "PIN3_3") (pintype "input"))
      (node (ref "PS1") (pin "7") (pinfunction "7_7") (pintype "input"))
      (node (ref "PS1") (pin "8") (pinfunction "8_8") (pintype "input"))
      (node (ref "PS1") (pin "9") (pinfunction "9_9") (pintype "input"))
      (node (ref "R31") (pin "1") (pinfunction "1_1") (pintype "input"))
      (node (ref "R32") (pin "1") (pinfunction "1_1") (pintype "input"))
      (node (ref "R33") (pin "1") (pinfunction "1_1") (pintype "input"))
      (node (ref "SW1") (pin "3") (pinfunction "C_3") (pintype "input"))
      (node (ref "SW1") (pin "4") (pinfunction "D_4") (pintype "input"))
      (node (ref "SW2") (pin "3") (pinfunction "C_3") (pintype "input"))
      (node (ref "SW2") (pin "4") (pinfunction "D_4") (pintype "input"))
      (node (ref "U1") (pin "1") (pinfunction "GND_1") (pintype "input"))
      (node (ref "U2") (pin "5") (pinfunction "GND_5") (pintype "input"))
      (node (ref "U5") (pin "19") (pinfunction "TESTEN_19") (pintype "input"))
      (node (ref "U5") (pin "57") (pinfunction "GND_57") (pintype "bidirectional"))
      (node (ref "U6") (pin "4") (pinfunction "GND_4") (pintype "input"))
      (node (ref "USB2") (pin "A1") (pinfunction "GND_A1") (pintype "input"))
      (node (ref "USB2") (pin "A12") (pinfunction "GND_A12") (pintype "input"))
      (node (ref "USB2") (pin "B1") (pinfunction "GND_B1") (pintype "input"))
      (node (ref "USB2") (pin "B12") (pinfunction "GND_B12") (pintype "input"))
      (node (ref "X1") (pin "2") (pinfunction "GND_2") (pintype "input"))
      (node (ref "X1") (pin "4") (pinfunction "GND_4") (pintype "input"))
    )
    (net (code "40") (name "Net-(C28-Pad2)") (class "Default")
      (node (ref "C28") (pin "2") (pinfunction "2_2") (pintype "input"))
      (node (ref "C30") (pin "1") (pinfunction "1_1") (pintype "input"))
      (node (ref "L1") (pin "1") (pinfunction "1_1") (pintype "input"))
      (node (ref "R34") (pin "2") (pinfunction "2_2") (pintype "input"))
    )
    (net (code "41") (name "Net-(C29-Pad2)") (class "Default")
      (node (ref "C29") (pin "2") (pinfunction "2_2") (pintype "input"))
      (node (ref "C31") (pin "1") (pinfunction "1_1") (pintype "input"))
      (node (ref "L2") (pin "1") (pinfunction "1_1") (pintype "input"))
      (node (ref "R35") (pin "2") (pinfunction "2_2") (pintype "input"))
    )
    (net (code "42") (name "Net-(C30-Pad2)") (class "Default")
      (node (ref "C30") (pin "2") (pinfunction "2_2") (pintype "input"))
      (node (ref "C32") (pin "2") (pinfunction "2_2") (pintype "input"))
      (node (ref "CN1") (pin "2") (pinfunction "2_2") (pintype "input"))
      (node (ref "CN1") (pin "6") (pinfunction "6_6") (pintype "input"))
      (node (ref "L1") (pin "2") (pinfunction "2_2") (pintype "input"))
    )
    (net (code "43") (name "Net-(C31-Pad2)") (class "Default")
      (node (ref "C31") (pin "2") (pinfunction "2_2") (pintype "input"))
      (node (ref "C33") (pin "2") (pinfunction "2_2") (pintype "input"))
      (node (ref "CN1") (pin "5") (pinfunction "5_5") (pintype "input"))
      (node (ref "L2") (pin "2") (pinfunction "2_2") (pintype "input"))
    )
    (net (code "44") (name "Net-(DSUB1-Pad1)") (class "Default")
      (node (ref "DSUB1") (pin "1") (pinfunction "1_1") (pintype "input"))
      (node (ref "R14") (pin "2") (pinfunction "2_2") (pintype "input"))
    )
    (net (code "45") (name "Net-(DSUB1-Pad2)") (class "Default")
      (node (ref "DSUB1") (pin "2") (pinfunction "2_2") (pintype "input"))
      (node (ref "R15") (pin "2") (pinfunction "2_2") (pintype "input"))
      (node (ref "R38") (pin "2") (pinfunction "2_2") (pintype "input"))
    )
    (net (code "46") (name "Net-(DSUB1-Pad3)") (class "Default")
      (node (ref "DSUB1") (pin "3") (pinfunction "3_3") (pintype "input"))
      (node (ref "R13") (pin "2") (pinfunction "2_2") (pintype "input"))
    )
    (net (code "47") (name "Net-(LED1-+)") (class "Default")
      (node (ref "LED1") (pin "2") (pinfunction "+_2") (pintype "input"))
      (node (ref "R3") (pin "2") (pinfunction "2_2") (pintype "input"))
    )
    (net (code "48") (name "Net-(PS1-PIN1)") (class "Default")
      (node (ref "PS1") (pin "1") (pinfunction "PIN1_1") (pintype "input"))
      (node (ref "Q2") (pin "3") (pinfunction "D_3") (pintype "input"))
      (node (ref "R27") (pin "1") (pinfunction "1_1") (pintype "input"))
    )
    (net (code "49") (name "Net-(PS1-PIN5)") (class "Default")
      (node (ref "PS1") (pin "5") (pinfunction "PIN5_5") (pintype "input"))
      (node (ref "Q1") (pin "3") (pinfunction "D_3") (pintype "input"))
      (node (ref "R25") (pin "1") (pinfunction "1_1") (pintype "input"))
    )
    (net (code "50") (name "Net-(R33-Pad2)") (class "Default")
      (node (ref "R33") (pin "2") (pinfunction "2_2") (pintype "input"))
      (node (ref "USB2") (pin "1") (pinfunction "EP_1") (pintype "input"))
      (node (ref "USB2") (pin "2") (pinfunction "EP_2") (pintype "input"))
      (node (ref "USB2") (pin "3") (pinfunction "EP_3") (pintype "input"))
      (node (ref "USB2") (pin "4") (pinfunction "EP_4") (pintype "input"))
    )
    (net (code "51") (name "Net-(SW2-A)") (class "Default")
      (node (ref "R4") (pin "2") (pinfunction "2_2") (pintype "input"))
      (node (ref "SW2") (pin "1") (pinfunction "A_1") (pintype "input"))
      (node (ref "SW2") (pin "2") (pinfunction "B_2") (pintype "input"))
    )
    (net (code "52") (name "Net-(U2-VBAT)") (class "Default")
      (node (ref "BT1") (pin "1") (pinfunction "1_1") (pintype "input"))
      (node (ref "U2") (pin "6") (pinfunction "VBAT_6") (pintype "input"))
    )
    (net (code "53") (name "Net-(U5-QSPI_SCLK)") (class "Default")
      (node (ref "U5") (pin "52") (pinfunction "QSPI_SCLK_52") (pintype "output"))
      (node (ref "U6") (pin "6") (pinfunction "CLK_6") (pintype "input"))
    )
    (net (code "54") (name "Net-(U5-QSPI_SD0)") (class "Default")
      (node (ref "U5") (pin "53") (pinfunction "QSPI_SD0_53") (pintype "bidirectional"))
      (node (ref "U6") (pin "5") (pinfunction "DI_5") (pintype "input"))
    )
    (net (code "55") (name "Net-(U5-QSPI_SD1)") (class "Default")
      (node (ref "U5") (pin "55") (pinfunction "QSPI_SD1_55") (pintype "bidirectional"))
      (node (ref "U6") (pin "2") (pinfunction "DO_2") (pintype "input"))
    )
    (net (code "56") (name "Net-(U5-QSPI_SD2)") (class "Default")
      (node (ref "U5") (pin "54") (pinfunction "QSPI_SD2_54") (pintype "bidirectional"))
      (node (ref "U6") (pin "3") (pinfunction "IO2_3") (pintype "input"))
    )
    (net (code "57") (name "Net-(U5-QSPI_SD3)") (class "Default")
      (node (ref "U5") (pin "51") (pinfunction "QSPI_SD3_51") (pintype "bidirectional"))
      (node (ref "U6") (pin "7") (pinfunction "IO3_7") (pintype "input"))
    )
    (net (code "58") (name "Net-(U5-QSPI_SS)") (class "Default")
      (node (ref "R23") (pin "1") (pinfunction "1_1") (pintype "input"))
      (node (ref "R4") (pin "1") (pinfunction "1_1") (pintype "input"))
      (node (ref "U5") (pin "56") (pinfunction "QSPI_SS_56") (pintype "bidirectional"))
      (node (ref "U6") (pin "1") (pinfunction "CS#_1") (pintype "input"))
    )
    (net (code "59") (name "Net-(U5-USB_DM)") (class "Default")
      (node (ref "R37") (pin "1") (pinfunction "1_1") (pintype "input"))
      (node (ref "U5") (pin "46") (pinfunction "USB_DM_46") (pintype "bidirectional"))
    )
    (net (code "60") (name "Net-(U5-USB_DP)") (class "Default")
      (node (ref "R36") (pin "1") (pinfunction "1_1") (pintype "input"))
      (node (ref "U5") (pin "47") (pinfunction "USB_DP_47") (pintype "bidirectional"))
    )
    (net (code "61") (name "Net-(U5-XIN)") (class "Default")
      (node (ref "C3") (pin "2") (pinfunction "2_2") (pintype "input"))
      (node (ref "U5") (pin "20") (pinfunction "XIN_20") (pintype "input"))
      (node (ref "X1") (pin "3") (pinfunction "OSC2_3") (pintype "input"))
    )
    (net (code "62") (name "Net-(U5-XOUT)") (class "Default")
      (node (ref "R5") (pin "2") (pinfunction "2_2") (pintype "input"))
      (node (ref "U5") (pin "21") (pinfunction "XOUT_21") (pintype "input"))
    )
    (net (code "63") (name "Net-(USB2-CC1)") (class "Default")
      (node (ref "R32") (pin "2") (pinfunction "2_2") (pintype "input"))
      (node (ref "USB2") (pin "A5") (pinfunction "CC1_A5") (pintype "input"))
    )
    (net (code "64") (name "Net-(USB2-CC2)") (class "Default")
      (node (ref "R31") (pin "2") (pinfunction "2_2") (pintype "input"))
      (node (ref "USB2") (pin "B5") (pinfunction "CC2_B5") (pintype "input"))
    )
    (net (code "65") (name "Net-(X1-OSC1)") (class "Default")
      (node (ref "C4") (pin "2") (pinfunction "2_2") (pintype "input"))
      (node (ref "R5") (pin "1") (pinfunction "1_1") (pintype "input"))
      (node (ref "X1") (pin "1") (pinfunction "OSC1_1") (pintype "input"))
    )
    (net (code "66") (name "VCC") (class "Default")
      (node (ref "C10") (pin "2") (pinfunction "2_2") (pintype "input"))
      (node (ref "C11") (pin "2") (pinfunction "2_2") (pintype "input"))
      (node (ref "C12") (pin "2") (pinfunction "2_2") (pintype "input"))
      (node (ref "C18") (pin "2") (pinfunction "2_2") (pintype "input"))
      (node (ref "C20") (pin "2") (pinfunction "2_2") (pintype "input"))
      (node (ref "C22") (pin "2") (pinfunction "2_2") (pintype "input"))
      (node (ref "C26") (pin "2") (pinfunction "2_2") (pintype "input"))
      (node (ref "C5") (pin "2") (pinfunction "2_2") (pintype "input"))
      (node (ref "C6") (pin "2") (pinfunction "2_2") (pintype "input"))
      (node (ref "C7") (pin "2") (pinfunction "2_2") (pintype "input"))
      (node (ref "C8") (pin "2") (pinfunction "2_2") (pintype "input"))
      (node (ref "C9") (pin "2") (pinfunction "2_2") (pintype "input"))
      (node (ref "J2") (pin "5") (pinfunction "5_5") (pintype "input"))
      (node (ref "J2") (pin "6") (pinfunction "6_6") (pintype "input"))
      (node (ref "Q1") (pin "1") (pinfunction "G_1") (pintype "input"))
      (node (ref "Q2") (pin "1") (pinfunction "G_1") (pintype "input"))
      (node (ref "R11") (pin "2") (pinfunction "2_2") (pintype "input"))
      (node (ref "R12") (pin "2") (pinfunction "2_2") (pintype "input"))
      (node (ref "R23") (pin "2") (pinfunction "2_2") (pintype "input"))
      (node (ref "R24") (pin "2") (pinfunction "2_2") (pintype "input"))
      (node (ref "R26") (pin "2") (pinfunction "2_2") (pintype "input"))
      (node (ref "R28") (pin "2") (pinfunction "2_2") (pintype "input"))
      (node (ref "R29") (pin "1") (pinfunction "1_1") (pintype "input"))
      (node (ref "U1") (pin "2") (pinfunction "VOUT_2") (pintype "input"))
      (node (ref "U1") (pin "4") (pinfunction "VOUT_4") (pintype "input"))
      (node (ref "U2") (pin "2") (pinfunction "VCC_2") (pintype "input"))
      (node (ref "U2") (pin "4") (pinfunction "RST#_4") (pintype "bidirectional"))
      (node (ref "U5") (pin "1") (pinfunction "IOVDD_1") (pintype "bidirectional"))
      (node (ref "U5") (pin "10") (pinfunction "IOVDD_10") (pintype "bidirectional"))
      (node (ref "U5") (pin "22") (pinfunction "IOVDD_22") (pintype "bidirectional"))
      (node (ref "U5") (pin "33") (pinfunction "IOVDD_33") (pintype "bidirectional"))
      (node (ref "U5") (pin "42") (pinfunction "IOVDD_42") (pintype "bidirectional"))
      (node (ref "U5") (pin "43") (pinfunction "ADC_AVDD_43") (pintype "bidirectional"))
      (node (ref "U5") (pin "44") (pinfunction "VREG_IN_44") (pintype "bidirectional"))
      (node (ref "U5") (pin "48") (pinfunction "USB_VDD_48") (pintype "bidirectional"))
      (node (ref "U5") (pin "49") (pinfunction "IOVDD_49") (pintype "bidirectional"))
      (node (ref "U6") (pin "8") (pinfunction "VCC_8") (pintype "input"))
    )
    (net (code "67") (name "unconnected-(CARD2-DAT1-Pad8)") (class "Default")
      (node (ref "CARD2") (pin "8") (pinfunction "DAT1_8") (pintype "input"))
    )
    (net (code "68") (name "unconnected-(CARD2-DAT2-Pad1)") (class "Default")
      (node (ref "CARD2") (pin "1") (pinfunction "DAT2_1") (pintype "input"))
    )
    (net (code "69") (name "unconnected-(CARD2-PadCD)") (class "Default")
      (node (ref "CARD2") (pin "CD") (pinfunction "CD_CD") (pintype "input"))
    )
    (net (code "70") (name "unconnected-(DSUB1-Pad4)") (class "Default")
      (node (ref "DSUB1") (pin "4") (pinfunction "4_4") (pintype "input+no_connect"))
    )
    (net (code "71") (name "unconnected-(DSUB1-Pad9)") (class "Default")
      (node (ref "DSUB1") (pin "9") (pinfunction "9_9") (pintype "input+no_connect"))
    )
    (net (code "72") (name "unconnected-(DSUB1-Pad11)") (class "Default")
      (node (ref "DSUB1") (pin "11") (pinfunction "11_11") (pintype "input+no_connect"))
    )
    (net (code "73") (name "unconnected-(DSUB1-Pad12)") (class "Default")
      (node (ref "DSUB1") (pin "12") (pinfunction "12_12") (pintype "input+no_connect"))
    )
    (net (code "74") (name "unconnected-(DSUB1-Pad15)") (class "Default")
      (node (ref "DSUB1") (pin "15") (pinfunction "15_15") (pintype "input+no_connect"))
    )
    (net (code "75") (name "unconnected-(J2-Pad4)") (class "Default")
      (node (ref "J2") (pin "4") (pinfunction "4_4") (pintype "input+no_connect"))
    )
    (net (code "76") (name "unconnected-(PS1-PIN2-Pad2)") (class "Default")
      (node (ref "PS1") (pin "2") (pinfunction "PIN2_2") (pintype "input+no_connect"))
    )
    (net (code "77") (name "unconnected-(PS1-PIN6-Pad6)") (class "Default")
      (node (ref "PS1") (pin "6") (pinfunction "PIN6_6") (pintype "input+no_connect"))
    )
    (net (code "78") (name "unconnected-(U2-32kHz-Pad1)") (class "Default")
      (node (ref "U2") (pin "1") (pinfunction "32kHz_1") (pintype "input+no_connect"))
    )
    (net (code "79") (name "unconnected-(U2-INT#{slash}SQW-Pad3)") (class "Default")
      (node (ref "U2") (pin "3") (pinfunction "INT#/SQW_3") (pintype "bidirectional+no_connect"))
    )
    (net (code "80") (name "unconnected-(U5-SWCLK-Pad24)") (class "Default")
      (node (ref "U5") (pin "24") (pinfunction "SWCLK_24") (pintype "output+no_connect"))
    )
    (net (code "81") (name "unconnected-(U5-SWD-Pad25)") (class "Default")
      (node (ref "U5") (pin "25") (pinfunction "SWD_25") (pintype "bidirectional+no_connect"))
    )
    (net (code "82") (name "unconnected-(USB2-SUB1-PadA8)") (class "Default")
      (node (ref "USB2") (pin "A8") (pinfunction "SUB1_A8") (pintype "input+no_connect"))
    )
    (net (code "83") (name "unconnected-(USB2-SUB2-PadB8)") (class "Default")
      (node (ref "USB2") (pin "B8") (pinfunction "SUB2_B8") (pintype "input+no_connect"))
    )
  )
)
